# thermoscheme.net
KiCad netlist of a schematic drawn in EAGLE
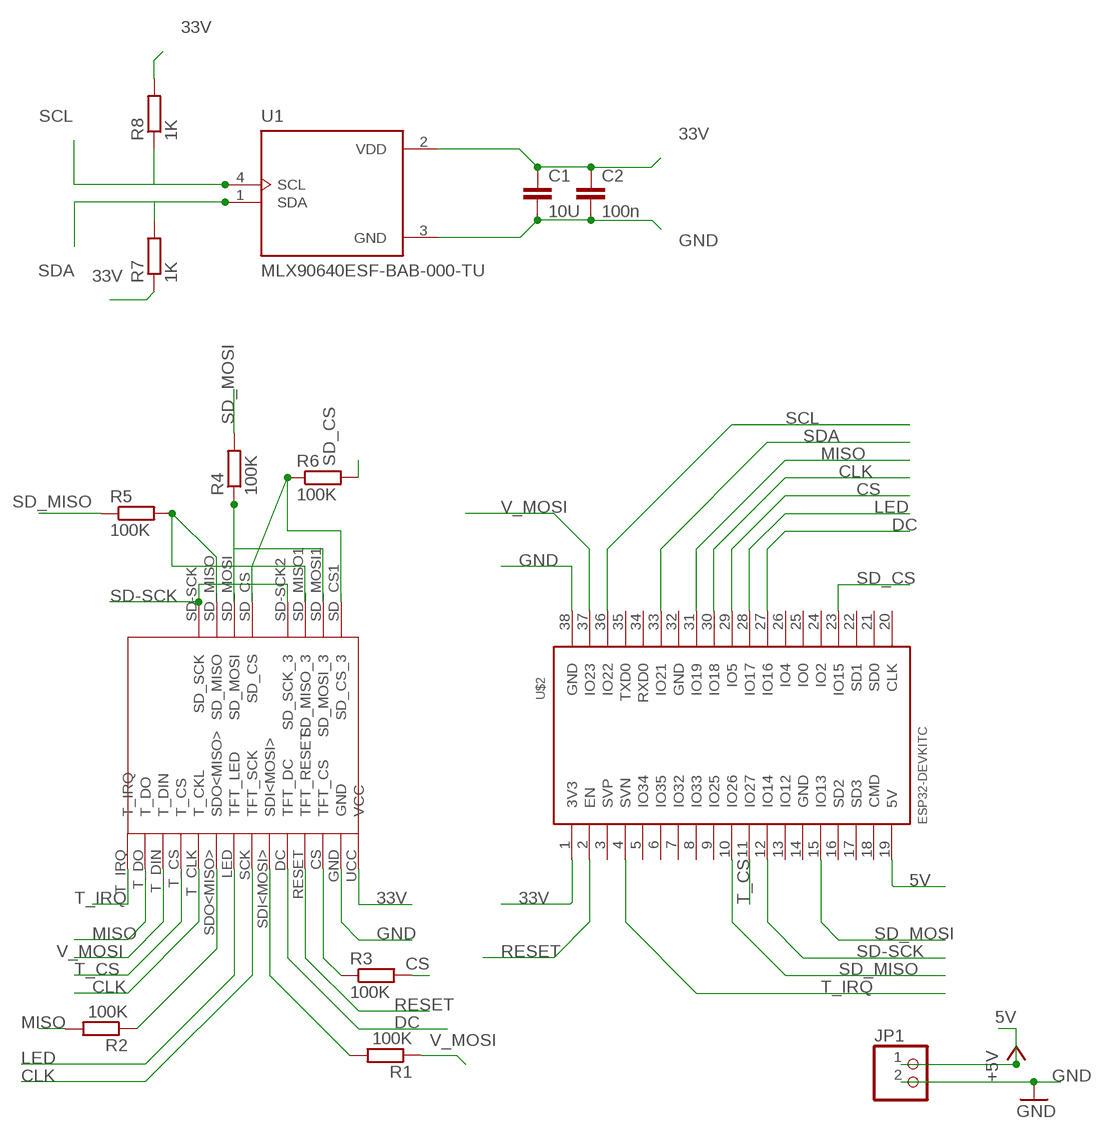
[diagram p0: schematic, sheet 1]

(export (version "E")
  (design (tool "Eeschema 10.0.6"))
  (components
    (comp (ref "C1")
      (value "10U")
      (footprint "eagle-import:C2.5-3")
      (libsource (lib "eagle-import") (part "C2,5-3"))
    )
    (comp (ref "C2")
      (value "100n")
      (footprint "eagle-import:C2.5-3")
      (libsource (lib "eagle-import") (part "C2,5-3"))
    )
    (comp (ref "JP1")
      (value "PINHD-1X2")
      (footprint "eagle-import:1X02")
      (libsource (lib "eagle-import") (part "PINHD-1X2"))
    )
    (comp (ref "R1")
      (value "100K")
      (footprint "eagle-import:0207_10")
      (libsource (lib "eagle-import") (part "R-EU_0207/10"))
    )
    (comp (ref "R2")
      (value "100K")
      (footprint "eagle-import:0207_10")
      (libsource (lib "eagle-import") (part "R-EU_0207/10"))
    )
    (comp (ref "R3")
      (value "100K")
      (footprint "eagle-import:0207_10")
      (libsource (lib "eagle-import") (part "R-EU_0207/10"))
    )
    (comp (ref "R4")
      (value "100K")
      (footprint "eagle-import:0207_10")
      (libsource (lib "eagle-import") (part "R-EU_0207/10"))
    )
    (comp (ref "R5")
      (value "100K")
      (footprint "eagle-import:0207_10")
      (libsource (lib "eagle-import") (part "R-EU_0207/10"))
    )
    (comp (ref "R6")
      (value "100K")
      (footprint "eagle-import:0207_10")
      (libsource (lib "eagle-import") (part "R-EU_0207/10"))
    )
    (comp (ref "R7")
      (value "1K")
      (footprint "eagle-import:0204_7")
      (libsource (lib "eagle-import") (part "R-EU_0204/7"))
    )
    (comp (ref "R8")
      (value "1K")
      (footprint "eagle-import:0204_7")
      (libsource (lib "eagle-import") (part "R-EU_0204/7"))
    )
    (comp (ref "U$2")
      (value "ESP32DEVKITC")
      (footprint "eagle-import:ESP32-DEVKITC")
      (libsource (lib "eagle-import") (part "ESP32DEVKITC"))
    )
    (comp (ref "U$3")
      (value "ILI9341")
      (footprint "eagle-import:ILI9341")
      (libsource (lib "eagle-import") (part "ILI9341"))
    )
    (comp (ref "U1")
      (value "MLX90640ESF-BAB-000-TU")
      (footprint "eagle-import:TO292P945H1165-4")
      (fields (field (name "MF") "Melexis Technologies NV"))
      (libsource (lib "eagle-import") (part "MLX90640ESF-BAB-000-TU"))
    )
  )
  (nets
    (net (code "1") (name "+5V") (class "Default")
      (node (ref "JP1") (pin "1") (pinfunction "1_1") (pintype "passive"))
      (node (ref "U$2") (pin "19") (pinfunction "5V_19") (pintype "bidirectional"))
    )
    (net (code "2") (name "/33V") (class "Default")
      (node (ref "C1") (pin "1") (pinfunction "1_1") (pintype "passive"))
      (node (ref "C2") (pin "1") (pinfunction "1_1") (pintype "passive"))
      (node (ref "R7") (pin "1") (pinfunction "1_1") (pintype "passive"))
      (node (ref "R8") (pin "2") (pinfunction "2_2") (pintype "passive"))
      (node (ref "U$2") (pin "1") (pinfunction "3V3_1") (pintype "bidirectional"))
      (node (ref "U$3") (pin "UCC") (pinfunction "VCC_UCC") (pintype "bidirectional"))
      (node (ref "U1") (pin "2") (pinfunction "VDD_2") (pintype "power_in"))
    )
    (net (code "3") (name "/CLK") (class "Default")
      (node (ref "U$2") (pin "30") (pinfunction "IO18_30") (pintype "bidirectional"))
      (node (ref "U$3") (pin "SCK") (pinfunction "TFT_SCK_SCK") (pintype "bidirectional"))
      (node (ref "U$3") (pin "T_CLK") (pinfunction "T_CKL_T_CLK") (pintype "bidirectional"))
    )
    (net (code "4") (name "/CS") (class "Default")
      (node (ref "R3") (pin "2") (pinfunction "2_2") (pintype "passive"))
      (node (ref "U$2") (pin "29") (pinfunction "IO5_29") (pintype "bidirectional"))
    )
    (net (code "5") (name "/DC") (class "Default")
      (node (ref "U$2") (pin "27") (pinfunction "IO16_27") (pintype "bidirectional"))
      (node (ref "U$3") (pin "DC") (pinfunction "TFT_DC_DC") (pintype "bidirectional"))
    )
    (net (code "6") (name "/LED") (class "Default")
      (node (ref "U$2") (pin "28") (pinfunction "IO17_28") (pintype "bidirectional"))
      (node (ref "U$3") (pin "LED") (pinfunction "TFT_LED_LED") (pintype "bidirectional"))
    )
    (net (code "7") (name "/MISO") (class "Default")
      (node (ref "R2") (pin "2") (pinfunction "2_2") (pintype "passive"))
      (node (ref "U$2") (pin "31") (pinfunction "IO19_31") (pintype "bidirectional"))
      (node (ref "U$3") (pin "T_DO") (pinfunction "T_DO_T_DO") (pintype "bidirectional"))
    )
    (net (code "8") (name "/RESET") (class "Default")
      (node (ref "U$2") (pin "2") (pinfunction "EN_2") (pintype "bidirectional"))
      (node (ref "U$3") (pin "RESET") (pinfunction "TFT_RESET_RESET") (pintype "bidirectional"))
    )
    (net (code "9") (name "/SCL") (class "Default")
      (node (ref "R8") (pin "1") (pinfunction "1_1") (pintype "passive"))
      (node (ref "U$2") (pin "36") (pinfunction "IO22_36") (pintype "bidirectional"))
      (node (ref "U1") (pin "4") (pinfunction "SCL_4") (pintype "input"))
    )
    (net (code "10") (name "/SD-SCK") (class "Default")
      (node (ref "U$2") (pin "12") (pinfunction "IO14_12") (pintype "bidirectional"))
      (node (ref "U$3") (pin "SD-SCK") (pinfunction "SD_SCK_SD-SCK") (pintype "bidirectional"))
      (node (ref "U$3") (pin "SD-SCK2") (pinfunction "SD_SCK_3_SD-SCK2") (pintype "bidirectional"))
    )
    (net (code "11") (name "/SDA") (class "Default")
      (node (ref "R7") (pin "2") (pinfunction "2_2") (pintype "passive"))
      (node (ref "U$2") (pin "33") (pinfunction "IO21_33") (pintype "bidirectional"))
      (node (ref "U1") (pin "1") (pinfunction "SDA_1") (pintype "bidirectional"))
    )
    (net (code "12") (name "/SD_CS") (class "Default")
      (node (ref "R6") (pin "2") (pinfunction "2_2") (pintype "passive"))
      (node (ref "U$2") (pin "23") (pinfunction "IO15_23") (pintype "bidirectional"))
    )
    (net (code "13") (name "/SD_MISO") (class "Default")
      (node (ref "R5") (pin "1") (pinfunction "1_1") (pintype "passive"))
      (node (ref "U$2") (pin "10") (pinfunction "IO26_10") (pintype "bidirectional"))
    )
    (net (code "14") (name "/SD_MOSI") (class "Default")
      (node (ref "R4") (pin "2") (pinfunction "2_2") (pintype "passive"))
      (node (ref "U$2") (pin "15") (pinfunction "IO13_15") (pintype "bidirectional"))
    )
    (net (code "15") (name "/T_CS") (class "Default")
      (node (ref "U$2") (pin "11") (pinfunction "IO27_11") (pintype "bidirectional"))
      (node (ref "U$3") (pin "T_CS") (pinfunction "T_CS_T_CS") (pintype "bidirectional"))
    )
    (net (code "16") (name "/T_IRQ") (class "Default")
      (node (ref "U$2") (pin "4") (pinfunction "SVN_4") (pintype "bidirectional"))
      (node (ref "U$3") (pin "T_IRQ") (pinfunction "T_IRQ_T_IRQ") (pintype "bidirectional"))
    )
    (net (code "17") (name "/V_MOSI") (class "Default")
      (node (ref "R1") (pin "1") (pinfunction "1_1") (pintype "passive"))
      (node (ref "U$2") (pin "37") (pinfunction "IO23_37") (pintype "bidirectional"))
      (node (ref "U$3") (pin "T_DIN") (pinfunction "T_DIN_T_DIN") (pintype "bidirectional"))
    )
    (net (code "18") (name "GND") (class "Default")
      (node (ref "C1") (pin "2") (pinfunction "2_2") (pintype "passive"))
      (node (ref "C2") (pin "2") (pinfunction "2_2") (pintype "passive"))
      (node (ref "JP1") (pin "2") (pinfunction "2_2") (pintype "passive"))
      (node (ref "U$2") (pin "38") (pinfunction "GND_38") (pintype "bidirectional"))
      (node (ref "U$3") (pin "GND") (pinfunction "GND_GND") (pintype "bidirectional"))
      (node (ref "U1") (pin "3") (pinfunction "GND_3") (pintype "power_in"))
    )
    (net (code "19") (name "Net-(R1-Pad2)") (class "Default")
      (node (ref "R1") (pin "2") (pinfunction "2_2") (pintype "passive"))
      (node (ref "U$3") (pin "SDI<MOSI>") (pinfunction "SDI<MOSI>_SDI<MOSI>") (pintype "bidirectional"))
    )
    (net (code "20") (name "Net-(R2-Pad1)") (class "Default")
      (node (ref "R2") (pin "1") (pinfunction "1_1") (pintype "passive"))
      (node (ref "U$3") (pin "SDO<MISO>") (pinfunction "SDO<MISO>_SDO<MISO>") (pintype "bidirectional"))
    )
    (net (code "21") (name "Net-(U$3-SD_CS_3)") (class "Default")
      (node (ref "R6") (pin "1") (pinfunction "1_1") (pintype "passive"))
      (node (ref "U$3") (pin "SD_CS") (pinfunction "SD_CS_SD_CS") (pintype "bidirectional"))
      (node (ref "U$3") (pin "SD_CS1") (pinfunction "SD_CS_3_SD_CS1") (pintype "bidirectional"))
    )
    (net (code "22") (name "Net-(U$3-SD_MISO_3)") (class "Default")
      (node (ref "R5") (pin "2") (pinfunction "2_2") (pintype "passive"))
      (node (ref "U$3") (pin "SD_MISO") (pinfunction "SD_MISO_SD_MISO") (pintype "bidirectional"))
      (node (ref "U$3") (pin "SD_MISO1") (pinfunction "SD_MISO_3_SD_MISO1") (pintype "bidirectional"))
    )
    (net (code "23") (name "Net-(U$3-SD_MOSI_3)") (class "Default")
      (node (ref "R4") (pin "1") (pinfunction "1_1") (pintype "passive"))
      (node (ref "U$3") (pin "SD_MOSI") (pinfunction "SD_MOSI_SD_MOSI") (pintype "bidirectional"))
      (node (ref "U$3") (pin "SD_MOSI1") (pinfunction "SD_MOSI_3_SD_MOSI1") (pintype "bidirectional"))
    )
    (net (code "24") (name "Net-(U$3-TFT_CS)") (class "Default")
      (node (ref "R3") (pin "1") (pinfunction "1_1") (pintype "passive"))
      (node (ref "U$3") (pin "CS") (pinfunction "TFT_CS_CS") (pintype "bidirectional"))
    )
    (net (code "25") (name "unconnected-(U$2-CLK-Pad20)") (class "Default")
      (node (ref "U$2") (pin "20") (pinfunction "CLK_20") (pintype "bidirectional"))
    )
    (net (code "26") (name "unconnected-(U$2-CMD-Pad18)") (class "Default")
      (node (ref "U$2") (pin "18") (pinfunction "CMD_18") (pintype "bidirectional"))
    )
    (net (code "27") (name "unconnected-(U$2-GND-Pad14)") (class "Default")
      (node (ref "U$2") (pin "14") (pinfunction "GND_14") (pintype "bidirectional"))
    )
    (net (code "28") (name "unconnected-(U$2-GND-Pad32)") (class "Default")
      (node (ref "U$2") (pin "32") (pinfunction "GND_32") (pintype "bidirectional"))
    )
    (net (code "29") (name "unconnected-(U$2-IO0-Pad25)") (class "Default")
      (node (ref "U$2") (pin "25") (pinfunction "IO0_25") (pintype "bidirectional"))
    )
    (net (code "30") (name "unconnected-(U$2-IO2-Pad24)") (class "Default")
      (node (ref "U$2") (pin "24") (pinfunction "IO2_24") (pintype "bidirectional"))
    )
    (net (code "31") (name "unconnected-(U$2-IO4-Pad26)") (class "Default")
      (node (ref "U$2") (pin "26") (pinfunction "IO4_26") (pintype "bidirectional"))
    )
    (net (code "32") (name "unconnected-(U$2-IO12-Pad13)") (class "Default")
      (node (ref "U$2") (pin "13") (pinfunction "IO12_13") (pintype "bidirectional"))
    )
    (net (code "33") (name "unconnected-(U$2-IO25-Pad9)") (class "Default")
      (node (ref "U$2") (pin "9") (pinfunction "IO25_9") (pintype "bidirectional"))
    )
    (net (code "34") (name "unconnected-(U$2-IO32-Pad7)") (class "Default")
      (node (ref "U$2") (pin "7") (pinfunction "IO32_7") (pintype "bidirectional"))
    )
    (net (code "35") (name "unconnected-(U$2-IO33-Pad8)") (class "Default")
      (node (ref "U$2") (pin "8") (pinfunction "IO33_8") (pintype "bidirectional"))
    )
    (net (code "36") (name "unconnected-(U$2-IO34-Pad5)") (class "Default")
      (node (ref "U$2") (pin "5") (pinfunction "IO34_5") (pintype "bidirectional"))
    )
    (net (code "37") (name "unconnected-(U$2-IO35-Pad6)") (class "Default")
      (node (ref "U$2") (pin "6") (pinfunction "IO35_6") (pintype "bidirectional"))
    )
    (net (code "38") (name "unconnected-(U$2-RXD0-Pad34)") (class "Default")
      (node (ref "U$2") (pin "34") (pinfunction "RXD0_34") (pintype "bidirectional"))
    )
    (net (code "39") (name "unconnected-(U$2-SD0-Pad21)") (class "Default")
      (node (ref "U$2") (pin "21") (pinfunction "SD0_21") (pintype "bidirectional"))
    )
    (net (code "40") (name "unconnected-(U$2-SD1-Pad22)") (class "Default")
      (node (ref "U$2") (pin "22") (pinfunction "SD1_22") (pintype "bidirectional"))
    )
    (net (code "41") (name "unconnected-(U$2-SD2-Pad16)") (class "Default")
      (node (ref "U$2") (pin "16") (pinfunction "SD2_16") (pintype "bidirectional"))
    )
    (net (code "42") (name "unconnected-(U$2-SD3-Pad17)") (class "Default")
      (node (ref "U$2") (pin "17") (pinfunction "SD3_17") (pintype "bidirectional"))
    )
    (net (code "43") (name "unconnected-(U$2-SVP-Pad3)") (class "Default")
      (node (ref "U$2") (pin "3") (pinfunction "SVP_3") (pintype "bidirectional"))
    )
    (net (code "44") (name "unconnected-(U$2-TXD0-Pad35)") (class "Default")
      (node (ref "U$2") (pin "35") (pinfunction "TXD0_35") (pintype "bidirectional"))
    )
  )
)
